# 5403833B.net
KiCad netlist of a schematic drawn in EAGLE
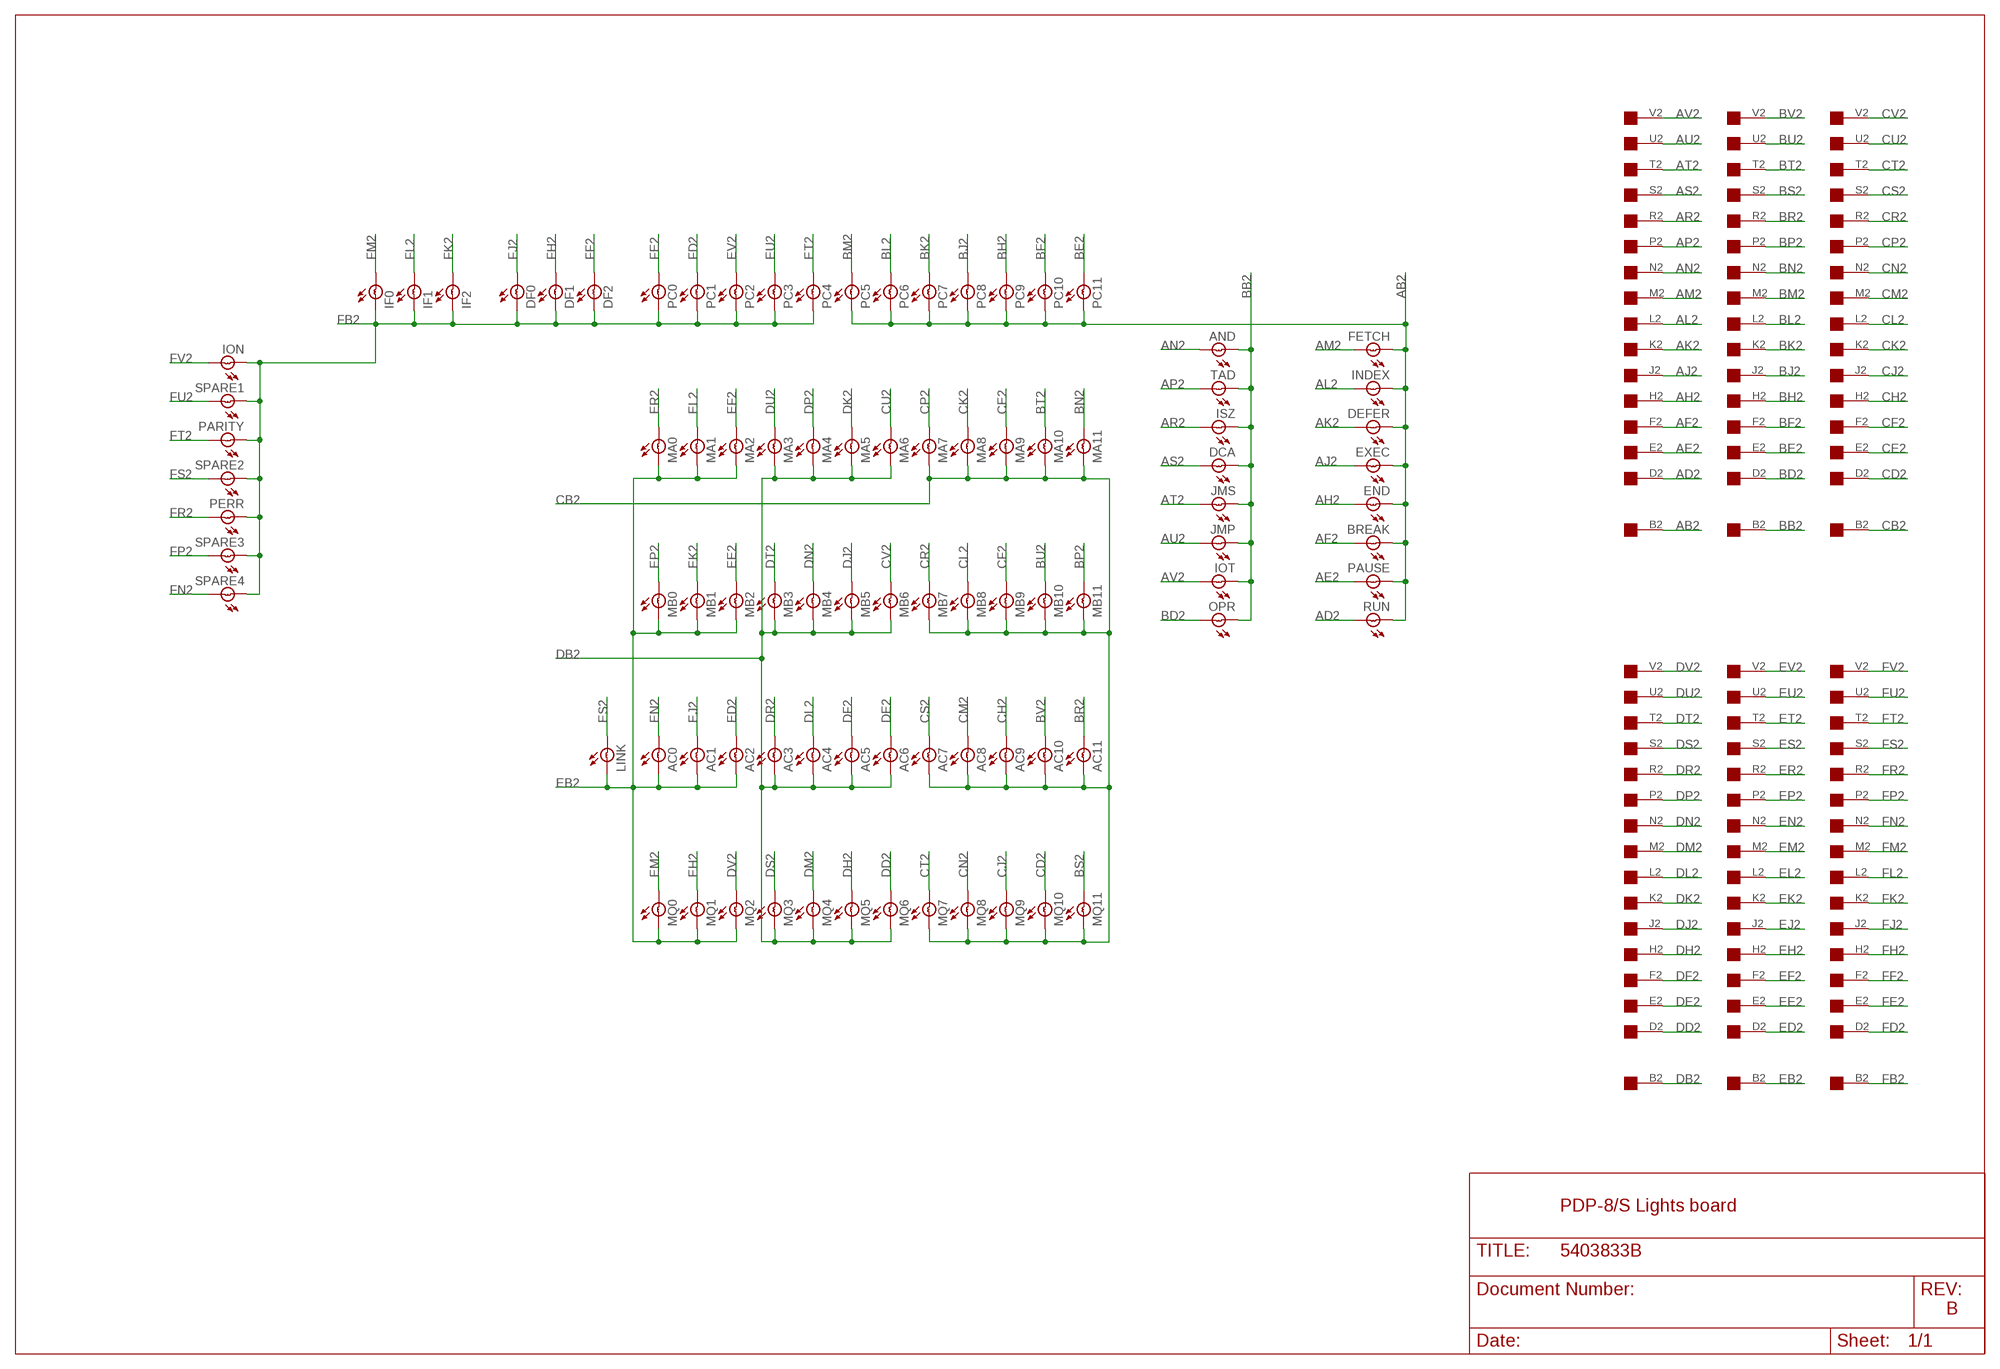
[diagram p0: schematic, sheet 1]

(export (version "E")
  (design (tool "Eeschema 10.0.6"))
  (components
    (comp (ref "A")
      (value "EDGE-1")
      (footprint "eagle-import:EDGE-CON1")
      (libsource (lib "eagle-import") (part "EDGE-1"))
    )
    (comp (ref "AC0")
      (value "BULB")
      (footprint "eagle-import:BULB")
      (libsource (lib "eagle-import") (part "BULB"))
    )
    (comp (ref "AC1")
      (value "BULB")
      (footprint "eagle-import:BULB")
      (libsource (lib "eagle-import") (part "BULB"))
    )
    (comp (ref "AC2")
      (value "BULB")
      (footprint "eagle-import:BULB")
      (libsource (lib "eagle-import") (part "BULB"))
    )
    (comp (ref "AC3")
      (value "BULB")
      (footprint "eagle-import:BULB")
      (libsource (lib "eagle-import") (part "BULB"))
    )
    (comp (ref "AC4")
      (value "BULB")
      (footprint "eagle-import:BULB")
      (libsource (lib "eagle-import") (part "BULB"))
    )
    (comp (ref "AC5")
      (value "BULB")
      (footprint "eagle-import:BULB")
      (libsource (lib "eagle-import") (part "BULB"))
    )
    (comp (ref "AC6")
      (value "BULB")
      (footprint "eagle-import:BULB")
      (libsource (lib "eagle-import") (part "BULB"))
    )
    (comp (ref "AC7")
      (value "BULB")
      (footprint "eagle-import:BULB")
      (libsource (lib "eagle-import") (part "BULB"))
    )
    (comp (ref "AC8")
      (value "BULB")
      (footprint "eagle-import:BULB")
      (libsource (lib "eagle-import") (part "BULB"))
    )
    (comp (ref "AC9")
      (value "BULB")
      (footprint "eagle-import:BULB")
      (libsource (lib "eagle-import") (part "BULB"))
    )
    (comp (ref "AC10")
      (value "BULB")
      (footprint "eagle-import:BULB")
      (libsource (lib "eagle-import") (part "BULB"))
    )
    (comp (ref "AC11")
      (value "BULB")
      (footprint "eagle-import:BULB")
      (libsource (lib "eagle-import") (part "BULB"))
    )
    (comp (ref "AND")
      (value "BULB")
      (footprint "eagle-import:BULB")
      (libsource (lib "eagle-import") (part "BULB"))
    )
    (comp (ref "B")
      (value "EDGE-1")
      (footprint "eagle-import:EDGE-CON1")
      (libsource (lib "eagle-import") (part "EDGE-1"))
    )
    (comp (ref "BREAK")
      (value "BULB")
      (footprint "eagle-import:BULB")
      (libsource (lib "eagle-import") (part "BULB"))
    )
    (comp (ref "C")
      (value "EDGE-1")
      (footprint "eagle-import:EDGE-CON1")
      (libsource (lib "eagle-import") (part "EDGE-1"))
    )
    (comp (ref "D")
      (value "EDGE-1")
      (footprint "eagle-import:EDGE-CON1")
      (libsource (lib "eagle-import") (part "EDGE-1"))
    )
    (comp (ref "DCA")
      (value "BULB")
      (footprint "eagle-import:BULB")
      (libsource (lib "eagle-import") (part "BULB"))
    )
    (comp (ref "DEFER")
      (value "BULB")
      (footprint "eagle-import:BULB")
      (libsource (lib "eagle-import") (part "BULB"))
    )
    (comp (ref "DF0")
      (value "BULB")
      (footprint "eagle-import:BULB")
      (libsource (lib "eagle-import") (part "BULB"))
    )
    (comp (ref "DF1")
      (value "BULB")
      (footprint "eagle-import:BULB")
      (libsource (lib "eagle-import") (part "BULB"))
    )
    (comp (ref "DF2")
      (value "BULB")
      (footprint "eagle-import:BULB")
      (libsource (lib "eagle-import") (part "BULB"))
    )
    (comp (ref "E")
      (value "EDGE-1")
      (footprint "eagle-import:EDGE-CON1")
      (libsource (lib "eagle-import") (part "EDGE-1"))
    )
    (comp (ref "END")
      (value "BULB")
      (footprint "eagle-import:BULB")
      (libsource (lib "eagle-import") (part "BULB"))
    )
    (comp (ref "EXEC")
      (value "BULB")
      (footprint "eagle-import:BULB")
      (libsource (lib "eagle-import") (part "BULB"))
    )
    (comp (ref "F")
      (value "EDGE-1")
      (footprint "eagle-import:EDGE-CON1")
      (libsource (lib "eagle-import") (part "EDGE-1"))
    )
    (comp (ref "FETCH")
      (value "BULB")
      (footprint "eagle-import:BULB")
      (libsource (lib "eagle-import") (part "BULB"))
    )
    (comp (ref "IF0")
      (value "BULB")
      (footprint "eagle-import:BULB")
      (libsource (lib "eagle-import") (part "BULB"))
    )
    (comp (ref "IF1")
      (value "BULB")
      (footprint "eagle-import:BULB")
      (libsource (lib "eagle-import") (part "BULB"))
    )
    (comp (ref "IF2")
      (value "BULB")
      (footprint "eagle-import:BULB")
      (libsource (lib "eagle-import") (part "BULB"))
    )
    (comp (ref "INDEX")
      (value "BULB")
      (footprint "eagle-import:BULB")
      (libsource (lib "eagle-import") (part "BULB"))
    )
    (comp (ref "ION")
      (value "BULB")
      (footprint "eagle-import:BULB")
      (libsource (lib "eagle-import") (part "BULB"))
    )
    (comp (ref "IOT")
      (value "BULB")
      (footprint "eagle-import:BULB")
      (libsource (lib "eagle-import") (part "BULB"))
    )
    (comp (ref "ISZ")
      (value "BULB")
      (footprint "eagle-import:BULB")
      (libsource (lib "eagle-import") (part "BULB"))
    )
    (comp (ref "JMP")
      (value "BULB")
      (footprint "eagle-import:BULB")
      (libsource (lib "eagle-import") (part "BULB"))
    )
    (comp (ref "JMS")
      (value "BULB")
      (footprint "eagle-import:BULB")
      (libsource (lib "eagle-import") (part "BULB"))
    )
    (comp (ref "LINK")
      (value "BULB")
      (footprint "eagle-import:BULB")
      (libsource (lib "eagle-import") (part "BULB"))
    )
    (comp (ref "MA0")
      (value "BULB")
      (footprint "eagle-import:BULB")
      (libsource (lib "eagle-import") (part "BULB"))
    )
    (comp (ref "MA1")
      (value "BULB")
      (footprint "eagle-import:BULB")
      (libsource (lib "eagle-import") (part "BULB"))
    )
    (comp (ref "MA2")
      (value "BULB")
      (footprint "eagle-import:BULB")
      (libsource (lib "eagle-import") (part "BULB"))
    )
    (comp (ref "MA3")
      (value "BULB")
      (footprint "eagle-import:BULB")
      (libsource (lib "eagle-import") (part "BULB"))
    )
    (comp (ref "MA4")
      (value "BULB")
      (footprint "eagle-import:BULB")
      (libsource (lib "eagle-import") (part "BULB"))
    )
    (comp (ref "MA5")
      (value "BULB")
      (footprint "eagle-import:BULB")
      (libsource (lib "eagle-import") (part "BULB"))
    )
    (comp (ref "MA6")
      (value "BULB")
      (footprint "eagle-import:BULB")
      (libsource (lib "eagle-import") (part "BULB"))
    )
    (comp (ref "MA7")
      (value "BULB")
      (footprint "eagle-import:BULB")
      (libsource (lib "eagle-import") (part "BULB"))
    )
    (comp (ref "MA8")
      (value "BULB")
      (footprint "eagle-import:BULB")
      (libsource (lib "eagle-import") (part "BULB"))
    )
    (comp (ref "MA9")
      (value "BULB")
      (footprint "eagle-import:BULB")
      (libsource (lib "eagle-import") (part "BULB"))
    )
    (comp (ref "MA10")
      (value "BULB")
      (footprint "eagle-import:BULB")
      (libsource (lib "eagle-import") (part "BULB"))
    )
    (comp (ref "MA11")
      (value "BULB")
      (footprint "eagle-import:BULB")
      (libsource (lib "eagle-import") (part "BULB"))
    )
    (comp (ref "MB0")
      (value "BULB")
      (footprint "eagle-import:BULB")
      (libsource (lib "eagle-import") (part "BULB"))
    )
    (comp (ref "MB1")
      (value "BULB")
      (footprint "eagle-import:BULB")
      (libsource (lib "eagle-import") (part "BULB"))
    )
    (comp (ref "MB2")
      (value "BULB")
      (footprint "eagle-import:BULB")
      (libsource (lib "eagle-import") (part "BULB"))
    )
    (comp (ref "MB3")
      (value "BULB")
      (footprint "eagle-import:BULB")
      (libsource (lib "eagle-import") (part "BULB"))
    )
    (comp (ref "MB4")
      (value "BULB")
      (footprint "eagle-import:BULB")
      (libsource (lib "eagle-import") (part "BULB"))
    )
    (comp (ref "MB5")
      (value "BULB")
      (footprint "eagle-import:BULB")
      (libsource (lib "eagle-import") (part "BULB"))
    )
    (comp (ref "MB6")
      (value "BULB")
      (footprint "eagle-import:BULB")
      (libsource (lib "eagle-import") (part "BULB"))
    )
    (comp (ref "MB7")
      (value "BULB")
      (footprint "eagle-import:BULB")
      (libsource (lib "eagle-import") (part "BULB"))
    )
    (comp (ref "MB8")
      (value "BULB")
      (footprint "eagle-import:BULB")
      (libsource (lib "eagle-import") (part "BULB"))
    )
    (comp (ref "MB9")
      (value "BULB")
      (footprint "eagle-import:BULB")
      (libsource (lib "eagle-import") (part "BULB"))
    )
    (comp (ref "MB10")
      (value "BULB")
      (footprint "eagle-import:BULB")
      (libsource (lib "eagle-import") (part "BULB"))
    )
    (comp (ref "MB11")
      (value "BULB")
      (footprint "eagle-import:BULB")
      (libsource (lib "eagle-import") (part "BULB"))
    )
    (comp (ref "MQ0")
      (value "BULB")
      (footprint "eagle-import:BULB")
      (libsource (lib "eagle-import") (part "BULB"))
    )
    (comp (ref "MQ1")
      (value "BULB")
      (footprint "eagle-import:BULB")
      (libsource (lib "eagle-import") (part "BULB"))
    )
    (comp (ref "MQ2")
      (value "BULB")
      (footprint "eagle-import:BULB")
      (libsource (lib "eagle-import") (part "BULB"))
    )
    (comp (ref "MQ3")
      (value "BULB")
      (footprint "eagle-import:BULB")
      (libsource (lib "eagle-import") (part "BULB"))
    )
    (comp (ref "MQ4")
      (value "BULB")
      (footprint "eagle-import:BULB")
      (libsource (lib "eagle-import") (part "BULB"))
    )
    (comp (ref "MQ5")
      (value "BULB")
      (footprint "eagle-import:BULB")
      (libsource (lib "eagle-import") (part "BULB"))
    )
    (comp (ref "MQ6")
      (value "BULB")
      (footprint "eagle-import:BULB")
      (libsource (lib "eagle-import") (part "BULB"))
    )
    (comp (ref "MQ7")
      (value "BULB")
      (footprint "eagle-import:BULB")
      (libsource (lib "eagle-import") (part "BULB"))
    )
    (comp (ref "MQ8")
      (value "BULB")
      (footprint "eagle-import:BULB")
      (libsource (lib "eagle-import") (part "BULB"))
    )
    (comp (ref "MQ9")
      (value "BULB")
      (footprint "eagle-import:BULB")
      (libsource (lib "eagle-import") (part "BULB"))
    )
    (comp (ref "MQ10")
      (value "BULB")
      (footprint "eagle-import:BULB")
      (libsource (lib "eagle-import") (part "BULB"))
    )
    (comp (ref "MQ11")
      (value "BULB")
      (footprint "eagle-import:BULB")
      (libsource (lib "eagle-import") (part "BULB"))
    )
    (comp (ref "OPR")
      (value "BULB")
      (footprint "eagle-import:BULB")
      (libsource (lib "eagle-import") (part "BULB"))
    )
    (comp (ref "PARITY")
      (value "BULB")
      (footprint "eagle-import:BULB")
      (libsource (lib "eagle-import") (part "BULB"))
    )
    (comp (ref "PAUSE")
      (value "BULB")
      (footprint "eagle-import:BULB")
      (libsource (lib "eagle-import") (part "BULB"))
    )
    (comp (ref "PC0")
      (value "BULB")
      (footprint "eagle-import:BULB")
      (libsource (lib "eagle-import") (part "BULB"))
    )
    (comp (ref "PC1")
      (value "BULB")
      (footprint "eagle-import:BULB")
      (libsource (lib "eagle-import") (part "BULB"))
    )
    (comp (ref "PC2")
      (value "BULB")
      (footprint "eagle-import:BULB")
      (libsource (lib "eagle-import") (part "BULB"))
    )
    (comp (ref "PC3")
      (value "BULB")
      (footprint "eagle-import:BULB")
      (libsource (lib "eagle-import") (part "BULB"))
    )
    (comp (ref "PC4")
      (value "BULB")
      (footprint "eagle-import:BULB")
      (libsource (lib "eagle-import") (part "BULB"))
    )
    (comp (ref "PC5")
      (value "BULB")
      (footprint "eagle-import:BULB")
      (libsource (lib "eagle-import") (part "BULB"))
    )
    (comp (ref "PC6")
      (value "BULB")
      (footprint "eagle-import:BULB")
      (libsource (lib "eagle-import") (part "BULB"))
    )
    (comp (ref "PC7")
      (value "BULB")
      (footprint "eagle-import:BULB")
      (libsource (lib "eagle-import") (part "BULB"))
    )
    (comp (ref "PC8")
      (value "BULB")
      (footprint "eagle-import:BULB")
      (libsource (lib "eagle-import") (part "BULB"))
    )
    (comp (ref "PC9")
      (value "BULB")
      (footprint "eagle-import:BULB")
      (libsource (lib "eagle-import") (part "BULB"))
    )
    (comp (ref "PC10")
      (value "BULB")
      (footprint "eagle-import:BULB")
      (libsource (lib "eagle-import") (part "BULB"))
    )
    (comp (ref "PC11")
      (value "BULB")
      (footprint "eagle-import:BULB")
      (libsource (lib "eagle-import") (part "BULB"))
    )
    (comp (ref "PERR")
      (value "BULB")
      (footprint "eagle-import:BULB")
      (libsource (lib "eagle-import") (part "BULB"))
    )
    (comp (ref "RUN")
      (value "BULB")
      (footprint "eagle-import:BULB")
      (libsource (lib "eagle-import") (part "BULB"))
    )
    (comp (ref "SPARE1")
      (value "BULB")
      (footprint "eagle-import:BULB")
      (libsource (lib "eagle-import") (part "BULB"))
    )
    (comp (ref "SPARE2")
      (value "BULB")
      (footprint "eagle-import:BULB")
      (libsource (lib "eagle-import") (part "BULB"))
    )
    (comp (ref "SPARE3")
      (value "BULB")
      (footprint "eagle-import:BULB")
      (libsource (lib "eagle-import") (part "BULB"))
    )
    (comp (ref "SPARE4")
      (value "BULB")
      (footprint "eagle-import:BULB")
      (libsource (lib "eagle-import") (part "BULB"))
    )
    (comp (ref "TAD")
      (value "BULB")
      (footprint "eagle-import:BULB")
      (libsource (lib "eagle-import") (part "BULB"))
    )
  )
  (nets
    (net (code "1") (name "/AB2") (class "Default")
      (node (ref "A") (pin "B2") (pinfunction "1_B2") (pintype "bidirectional"))
      (node (ref "BREAK") (pin "B") (pinfunction "B_B") (pintype "passive"))
      (node (ref "DEFER") (pin "B") (pinfunction "B_B") (pintype "passive"))
      (node (ref "END") (pin "B") (pinfunction "B_B") (pintype "passive"))
      (node (ref "EXEC") (pin "B") (pinfunction "B_B") (pintype "passive"))
      (node (ref "FETCH") (pin "B") (pinfunction "B_B") (pintype "passive"))
      (node (ref "INDEX") (pin "B") (pinfunction "B_B") (pintype "passive"))
      (node (ref "PAUSE") (pin "B") (pinfunction "B_B") (pintype "passive"))
      (node (ref "PC10") (pin "B") (pinfunction "B_B") (pintype "passive"))
      (node (ref "PC11") (pin "B") (pinfunction "B_B") (pintype "passive"))
      (node (ref "PC5") (pin "B") (pinfunction "B_B") (pintype "passive"))
      (node (ref "PC6") (pin "B") (pinfunction "B_B") (pintype "passive"))
      (node (ref "PC7") (pin "B") (pinfunction "B_B") (pintype "passive"))
      (node (ref "PC8") (pin "B") (pinfunction "B_B") (pintype "passive"))
      (node (ref "PC9") (pin "B") (pinfunction "B_B") (pintype "passive"))
      (node (ref "RUN") (pin "B") (pinfunction "B_B") (pintype "passive"))
    )
    (net (code "2") (name "/AD2") (class "Default")
      (node (ref "A") (pin "D2") (pinfunction "1_D2") (pintype "bidirectional"))
      (node (ref "RUN") (pin "A") (pinfunction "A_A") (pintype "passive"))
    )
    (net (code "3") (name "/AE2") (class "Default")
      (node (ref "A") (pin "E2") (pinfunction "1_E2") (pintype "bidirectional"))
      (node (ref "PAUSE") (pin "A") (pinfunction "A_A") (pintype "passive"))
    )
    (net (code "4") (name "/AF2") (class "Default")
      (node (ref "A") (pin "F2") (pinfunction "1_F2") (pintype "bidirectional"))
      (node (ref "BREAK") (pin "A") (pinfunction "A_A") (pintype "passive"))
    )
    (net (code "5") (name "/AH2") (class "Default")
      (node (ref "A") (pin "H2") (pinfunction "1_H2") (pintype "bidirectional"))
      (node (ref "END") (pin "A") (pinfunction "A_A") (pintype "passive"))
    )
    (net (code "6") (name "/AJ2") (class "Default")
      (node (ref "A") (pin "J2") (pinfunction "1_J2") (pintype "bidirectional"))
      (node (ref "EXEC") (pin "A") (pinfunction "A_A") (pintype "passive"))
    )
    (net (code "7") (name "/AK2") (class "Default")
      (node (ref "A") (pin "K2") (pinfunction "1_K2") (pintype "bidirectional"))
      (node (ref "DEFER") (pin "A") (pinfunction "A_A") (pintype "passive"))
    )
    (net (code "8") (name "/AL2") (class "Default")
      (node (ref "A") (pin "L2") (pinfunction "1_L2") (pintype "bidirectional"))
      (node (ref "INDEX") (pin "A") (pinfunction "A_A") (pintype "passive"))
    )
    (net (code "9") (name "/AM2") (class "Default")
      (node (ref "A") (pin "M2") (pinfunction "1_M2") (pintype "bidirectional"))
      (node (ref "FETCH") (pin "A") (pinfunction "A_A") (pintype "passive"))
    )
    (net (code "10") (name "/AN2") (class "Default")
      (node (ref "A") (pin "N2") (pinfunction "1_N2") (pintype "bidirectional"))
      (node (ref "AND") (pin "A") (pinfunction "A_A") (pintype "passive"))
    )
    (net (code "11") (name "/AP2") (class "Default")
      (node (ref "A") (pin "P2") (pinfunction "1_P2") (pintype "bidirectional"))
      (node (ref "TAD") (pin "A") (pinfunction "A_A") (pintype "passive"))
    )
    (net (code "12") (name "/AR2") (class "Default")
      (node (ref "A") (pin "R2") (pinfunction "1_R2") (pintype "bidirectional"))
      (node (ref "ISZ") (pin "A") (pinfunction "A_A") (pintype "passive"))
    )
    (net (code "13") (name "/AS2") (class "Default")
      (node (ref "A") (pin "S2") (pinfunction "1_S2") (pintype "bidirectional"))
      (node (ref "DCA") (pin "A") (pinfunction "A_A") (pintype "passive"))
    )
    (net (code "14") (name "/AT2") (class "Default")
      (node (ref "A") (pin "T2") (pinfunction "1_T2") (pintype "bidirectional"))
      (node (ref "JMS") (pin "A") (pinfunction "A_A") (pintype "passive"))
    )
    (net (code "15") (name "/AU2") (class "Default")
      (node (ref "A") (pin "U2") (pinfunction "1_U2") (pintype "bidirectional"))
      (node (ref "JMP") (pin "A") (pinfunction "A_A") (pintype "passive"))
    )
    (net (code "16") (name "/AV2") (class "Default")
      (node (ref "A") (pin "V2") (pinfunction "1_V2") (pintype "bidirectional"))
      (node (ref "IOT") (pin "A") (pinfunction "A_A") (pintype "passive"))
    )
    (net (code "17") (name "/BB2") (class "Default")
      (node (ref "AND") (pin "B") (pinfunction "B_B") (pintype "passive"))
      (node (ref "B") (pin "B2") (pinfunction "1_B2") (pintype "bidirectional"))
      (node (ref "DCA") (pin "B") (pinfunction "B_B") (pintype "passive"))
      (node (ref "IOT") (pin "B") (pinfunction "B_B") (pintype "passive"))
      (node (ref "ISZ") (pin "B") (pinfunction "B_B") (pintype "passive"))
      (node (ref "JMP") (pin "B") (pinfunction "B_B") (pintype "passive"))
      (node (ref "JMS") (pin "B") (pinfunction "B_B") (pintype "passive"))
      (node (ref "OPR") (pin "B") (pinfunction "B_B") (pintype "passive"))
      (node (ref "TAD") (pin "B") (pinfunction "B_B") (pintype "passive"))
    )
    (net (code "18") (name "/BD2") (class "Default")
      (node (ref "B") (pin "D2") (pinfunction "1_D2") (pintype "bidirectional"))
      (node (ref "OPR") (pin "A") (pinfunction "A_A") (pintype "passive"))
    )
    (net (code "19") (name "/BE2") (class "Default")
      (node (ref "B") (pin "E2") (pinfunction "1_E2") (pintype "bidirectional"))
      (node (ref "PC11") (pin "A") (pinfunction "A_A") (pintype "passive"))
    )
    (net (code "20") (name "/BF2") (class "Default")
      (node (ref "B") (pin "F2") (pinfunction "1_F2") (pintype "bidirectional"))
      (node (ref "PC10") (pin "A") (pinfunction "A_A") (pintype "passive"))
    )
    (net (code "21") (name "/BH2") (class "Default")
      (node (ref "B") (pin "H2") (pinfunction "1_H2") (pintype "bidirectional"))
      (node (ref "PC9") (pin "A") (pinfunction "A_A") (pintype "passive"))
    )
    (net (code "22") (name "/BJ2") (class "Default")
      (node (ref "B") (pin "J2") (pinfunction "1_J2") (pintype "bidirectional"))
      (node (ref "PC8") (pin "A") (pinfunction "A_A") (pintype "passive"))
    )
    (net (code "23") (name "/BK2") (class "Default")
      (node (ref "B") (pin "K2") (pinfunction "1_K2") (pintype "bidirectional"))
      (node (ref "PC7") (pin "A") (pinfunction "A_A") (pintype "passive"))
    )
    (net (code "24") (name "/BL2") (class "Default")
      (node (ref "B") (pin "L2") (pinfunction "1_L2") (pintype "bidirectional"))
      (node (ref "PC6") (pin "A") (pinfunction "A_A") (pintype "passive"))
    )
    (net (code "25") (name "/BM2") (class "Default")
      (node (ref "B") (pin "M2") (pinfunction "1_M2") (pintype "bidirectional"))
      (node (ref "PC5") (pin "A") (pinfunction "A_A") (pintype "passive"))
    )
    (net (code "26") (name "/BN2") (class "Default")
      (node (ref "B") (pin "N2") (pinfunction "1_N2") (pintype "bidirectional"))
      (node (ref "MA11") (pin "A") (pinfunction "A_A") (pintype "passive"))
    )
    (net (code "27") (name "/BP2") (class "Default")
      (node (ref "B") (pin "P2") (pinfunction "1_P2") (pintype "bidirectional"))
      (node (ref "MB11") (pin "A") (pinfunction "A_A") (pintype "passive"))
    )
    (net (code "28") (name "/BR2") (class "Default")
      (node (ref "AC11") (pin "A") (pinfunction "A_A") (pintype "passive"))
      (node (ref "B") (pin "R2") (pinfunction "1_R2") (pintype "bidirectional"))
    )
    (net (code "29") (name "/BS2") (class "Default")
      (node (ref "B") (pin "S2") (pinfunction "1_S2") (pintype "bidirectional"))
      (node (ref "MQ11") (pin "A") (pinfunction "A_A") (pintype "passive"))
    )
    (net (code "30") (name "/BT2") (class "Default")
      (node (ref "B") (pin "T2") (pinfunction "1_T2") (pintype "bidirectional"))
      (node (ref "MA10") (pin "A") (pinfunction "A_A") (pintype "passive"))
    )
    (net (code "31") (name "/BU2") (class "Default")
      (node (ref "B") (pin "U2") (pinfunction "1_U2") (pintype "bidirectional"))
      (node (ref "MB10") (pin "A") (pinfunction "A_A") (pintype "passive"))
    )
    (net (code "32") (name "/BV2") (class "Default")
      (node (ref "AC10") (pin "A") (pinfunction "A_A") (pintype "passive"))
      (node (ref "B") (pin "V2") (pinfunction "1_V2") (pintype "bidirectional"))
    )
    (net (code "33") (name "/CB2") (class "Default")
      (node (ref "AC10") (pin "B") (pinfunction "B_B") (pintype "passive"))
      (node (ref "AC11") (pin "B") (pinfunction "B_B") (pintype "passive"))
      (node (ref "AC7") (pin "B") (pinfunction "B_B") (pintype "passive"))
      (node (ref "AC8") (pin "B") (pinfunction "B_B") (pintype "passive"))
      (node (ref "AC9") (pin "B") (pinfunction "B_B") (pintype "passive"))
      (node (ref "C") (pin "B2") (pinfunction "1_B2") (pintype "bidirectional"))
      (node (ref "MA10") (pin "B") (pinfunction "B_B") (pintype "passive"))
      (node (ref "MA11") (pin "B") (pinfunction "B_B") (pintype "passive"))
      (node (ref "MA7") (pin "B") (pinfunction "B_B") (pintype "passive"))
      (node (ref "MA8") (pin "B") (pinfunction "B_B") (pintype "passive"))
      (node (ref "MA9") (pin "B") (pinfunction "B_B") (pintype "passive"))
      (node (ref "MB10") (pin "B") (pinfunction "B_B") (pintype "passive"))
      (node (ref "MB11") (pin "B") (pinfunction "B_B") (pintype "passive"))
      (node (ref "MB7") (pin "B") (pinfunction "B_B") (pintype "passive"))
      (node (ref "MB8") (pin "B") (pinfunction "B_B") (pintype "passive"))
      (node (ref "MB9") (pin "B") (pinfunction "B_B") (pintype "passive"))
      (node (ref "MQ10") (pin "B") (pinfunction "B_B") (pintype "passive"))
      (node (ref "MQ11") (pin "B") (pinfunction "B_B") (pintype "passive"))
      (node (ref "MQ7") (pin "B") (pinfunction "B_B") (pintype "passive"))
      (node (ref "MQ8") (pin "B") (pinfunction "B_B") (pintype "passive"))
      (node (ref "MQ9") (pin "B") (pinfunction "B_B") (pintype "passive"))
    )
    (net (code "34") (name "/CD2") (class "Default")
      (node (ref "C") (pin "D2") (pinfunction "1_D2") (pintype "bidirectional"))
      (node (ref "MQ10") (pin "A") (pinfunction "A_A") (pintype "passive"))
    )
    (net (code "35") (name "/CE2") (class "Default")
      (node (ref "C") (pin "E2") (pinfunction "1_E2") (pintype "bidirectional"))
      (node (ref "MA9") (pin "A") (pinfunction "A_A") (pintype "passive"))
    )
    (net (code "36") (name "/CF2") (class "Default")
      (node (ref "C") (pin "F2") (pinfunction "1_F2") (pintype "bidirectional"))
      (node (ref "MB9") (pin "A") (pinfunction "A_A") (pintype "passive"))
    )
    (net (code "37") (name "/CH2") (class "Default")
      (node (ref "AC9") (pin "A") (pinfunction "A_A") (pintype "passive"))
      (node (ref "C") (pin "H2") (pinfunction "1_H2") (pintype "bidirectional"))
    )
    (net (code "38") (name "/CJ2") (class "Default")
      (node (ref "C") (pin "J2") (pinfunction "1_J2") (pintype "bidirectional"))
      (node (ref "MQ9") (pin "A") (pinfunction "A_A") (pintype "passive"))
    )
    (net (code "39") (name "/CK2") (class "Default")
      (node (ref "C") (pin "K2") (pinfunction "1_K2") (pintype "bidirectional"))
      (node (ref "MA8") (pin "A") (pinfunction "A_A") (pintype "passive"))
    )
    (net (code "40") (name "/CL2") (class "Default")
      (node (ref "C") (pin "L2") (pinfunction "1_L2") (pintype "bidirectional"))
      (node (ref "MB8") (pin "A") (pinfunction "A_A") (pintype "passive"))
    )
    (net (code "41") (name "/CM2") (class "Default")
      (node (ref "AC8") (pin "A") (pinfunction "A_A") (pintype "passive"))
      (node (ref "C") (pin "M2") (pinfunction "1_M2") (pintype "bidirectional"))
    )
    (net (code "42") (name "/CN2") (class "Default")
      (node (ref "C") (pin "N2") (pinfunction "1_N2") (pintype "bidirectional"))
      (node (ref "MQ8") (pin "A") (pinfunction "A_A") (pintype "passive"))
    )
    (net (code "43") (name "/CP2") (class "Default")
      (node (ref "C") (pin "P2") (pinfunction "1_P2") (pintype "bidirectional"))
      (node (ref "MA7") (pin "A") (pinfunction "A_A") (pintype "passive"))
    )
    (net (code "44") (name "/CR2") (class "Default")
      (node (ref "C") (pin "R2") (pinfunction "1_R2") (pintype "bidirectional"))
      (node (ref "MB7") (pin "A") (pinfunction "A_A") (pintype "passive"))
    )
    (net (code "45") (name "/CS2") (class "Default")
      (node (ref "AC7") (pin "A") (pinfunction "A_A") (pintype "passive"))
      (node (ref "C") (pin "S2") (pinfunction "1_S2") (pintype "bidirectional"))
    )
    (net (code "46") (name "/CT2") (class "Default")
      (node (ref "C") (pin "T2") (pinfunction "1_T2") (pintype "bidirectional"))
      (node (ref "MQ7") (pin "A") (pinfunction "A_A") (pintype "passive"))
    )
    (net (code "47") (name "/CU2") (class "Default")
      (node (ref "C") (pin "U2") (pinfunction "1_U2") (pintype "bidirectional"))
      (node (ref "MA6") (pin "A") (pinfunction "A_A") (pintype "passive"))
    )
    (net (code "48") (name "/CV2") (class "Default")
      (node (ref "C") (pin "V2") (pinfunction "1_V2") (pintype "bidirectional"))
      (node (ref "MB6") (pin "A") (pinfunction "A_A") (pintype "passive"))
    )
    (net (code "49") (name "/DB2") (class "Default")
      (node (ref "AC3") (pin "B") (pinfunction "B_B") (pintype "passive"))
      (node (ref "AC4") (pin "B") (pinfunction "B_B") (pintype "passive"))
      (node (ref "AC5") (pin "B") (pinfunction "B_B") (pintype "passive"))
      (node (ref "AC6") (pin "B") (pinfunction "B_B") (pintype "passive"))
      (node (ref "D") (pin "B2") (pinfunction "1_B2") (pintype "bidirectional"))
      (node (ref "MA3") (pin "B") (pinfunction "B_B") (pintype "passive"))
      (node (ref "MA4") (pin "B") (pinfunction "B_B") (pintype "passive"))
      (node (ref "MA5") (pin "B") (pinfunction "B_B") (pintype "passive"))
      (node (ref "MA6") (pin "B") (pinfunction "B_B") (pintype "passive"))
      (node (ref "MB3") (pin "B") (pinfunction "B_B") (pintype "passive"))
      (node (ref "MB4") (pin "B") (pinfunction "B_B") (pintype "passive"))
      (node (ref "MB5") (pin "B") (pinfunction "B_B") (pintype "passive"))
      (node (ref "MB6") (pin "B") (pinfunction "B_B") (pintype "passive"))
      (node (ref "MQ3") (pin "B") (pinfunction "B_B") (pintype "passive"))
      (node (ref "MQ4") (pin "B") (pinfunction "B_B") (pintype "passive"))
      (node (ref "MQ5") (pin "B") (pinfunction "B_B") (pintype "passive"))
      (node (ref "MQ6") (pin "B") (pinfunction "B_B") (pintype "passive"))
    )
    (net (code "50") (name "/DD2") (class "Default")
      (node (ref "D") (pin "D2") (pinfunction "1_D2") (pintype "bidirectional"))
      (node (ref "MQ6") (pin "A") (pinfunction "A_A") (pintype "passive"))
    )
    (net (code "51") (name "/DE2") (class "Default")
      (node (ref "AC6") (pin "A") (pinfunction "A_A") (pintype "passive"))
      (node (ref "D") (pin "E2") (pinfunction "1_E2") (pintype "bidirectional"))
    )
    (net (code "52") (name "/DF2") (class "Default")
      (node (ref "AC5") (pin "A") (pinfunction "A_A") (pintype "passive"))
      (node (ref "D") (pin "F2") (pinfunction "1_F2") (pintype "bidirectional"))
    )
    (net (code "53") (name "/DH2") (class "Default")
      (node (ref "D") (pin "H2") (pinfunction "1_H2") (pintype "bidirectional"))
      (node (ref "MQ5") (pin "A") (pinfunction "A_A") (pintype "passive"))
    )
    (net (code "54") (name "/DJ2") (class "Default")
      (node (ref "D") (pin "J2") (pinfunction "1_J2") (pintype "bidirectional"))
      (node (ref "MB5") (pin "A") (pinfunction "A_A") (pintype "passive"))
    )
    (net (code "55") (name "/DK2") (class "Default")
      (node (ref "D") (pin "K2") (pinfunction "1_K2") (pintype "bidirectional"))
      (node (ref "MA5") (pin "A") (pinfunction "A_A") (pintype "passive"))
    )
    (net (code "56") (name "/DL2") (class "Default")
      (node (ref "AC4") (pin "A") (pinfunction "A_A") (pintype "passive"))
      (node (ref "D") (pin "L2") (pinfunction "1_L2") (pintype "bidirectional"))
    )
    (net (code "57") (name "/DM2") (class "Default")
      (node (ref "D") (pin "M2") (pinfunction "1_M2") (pintype "bidirectional"))
      (node (ref "MQ4") (pin "A") (pinfunction "A_A") (pintype "passive"))
    )
    (net (code "58") (name "/DN2") (class "Default")
      (node (ref "D") (pin "N2") (pinfunction "1_N2") (pintype "bidirectional"))
      (node (ref "MB4") (pin "A") (pinfunction "A_A") (pintype "passive"))
    )
    (net (code "59") (name "/DP2") (class "Default")
      (node (ref "D") (pin "P2") (pinfunction "1_P2") (pintype "bidirectional"))
      (node (ref "MA4") (pin "A") (pinfunction "A_A") (pintype "passive"))
    )
    (net (code "60") (name "/DR2") (class "Default")
      (node (ref "AC3") (pin "A") (pinfunction "A_A") (pintype "passive"))
      (node (ref "D") (pin "R2") (pinfunction "1_R2") (pintype "bidirectional"))
    )
    (net (code "61") (name "/DS2") (class "Default")
      (node (ref "D") (pin "S2") (pinfunction "1_S2") (pintype "bidirectional"))
      (node (ref "MQ3") (pin "A") (pinfunction "A_A") (pintype "passive"))
    )
    (net (code "62") (name "/DT2") (class "Default")
      (node (ref "D") (pin "T2") (pinfunction "1_T2") (pintype "bidirectional"))
      (node (ref "MB3") (pin "A") (pinfunction "A_A") (pintype "passive"))
    )
    (net (code "63") (name "/DU2") (class "Default")
      (node (ref "D") (pin "U2") (pinfunction "1_U2") (pintype "bidirectional"))
      (node (ref "MA3") (pin "A") (pinfunction "A_A") (pintype "passive"))
    )
    (net (code "64") (name "/DV2") (class "Default")
      (node (ref "D") (pin "V2") (pinfunction "1_V2") (pintype "bidirectional"))
      (node (ref "MQ2") (pin "A") (pinfunction "A_A") (pintype "passive"))
    )
    (net (code "65") (name "/EB2") (class "Default")
      (node (ref "AC0") (pin "B") (pinfunction "B_B") (pintype "passive"))
      (node (ref "AC1") (pin "B") (pinfunction "B_B") (pintype "passive"))
      (node (ref "AC2") (pin "B") (pinfunction "B_B") (pintype "passive"))
      (node (ref "E") (pin "B2") (pinfunction "1_B2") (pintype "bidirectional"))
      (node (ref "LINK") (pin "B") (pinfunction "B_B") (pintype "passive"))
      (node (ref "MA0") (pin "B") (pinfunction "B_B") (pintype "passive"))
      (node (ref "MA1") (pin "B") (pinfunction "B_B") (pintype "passive"))
      (node (ref "MA2") (pin "B") (pinfunction "B_B") (pintype "passive"))
      (node (ref "MB0") (pin "B") (pinfunction "B_B") (pintype "passive"))
      (node (ref "MB1") (pin "B") (pinfunction "B_B") (pintype "passive"))
      (node (ref "MB2") (pin "B") (pinfunction "B_B") (pintype "passive"))
      (node (ref "MQ0") (pin "B") (pinfunction "B_B") (pintype "passive"))
      (node (ref "MQ1") (pin "B") (pinfunction "B_B") (pintype "passive"))
      (node (ref "MQ2") (pin "B") (pinfunction "B_B") (pintype "passive"))
    )
    (net (code "66") (name "/ED2") (class "Default")
      (node (ref "AC2") (pin "A") (pinfunction "A_A") (pintype "passive"))
      (node (ref "E") (pin "D2") (pinfunction "1_D2") (pintype "bidirectional"))
    )
    (net (code "67") (name "/EE2") (class "Default")
      (node (ref "E") (pin "E2") (pinfunction "1_E2") (pintype "bidirectional"))
      (node (ref "MB2") (pin "A") (pinfunction "A_A") (pintype "passive"))
    )
    (net (code "68") (name "/EF2") (class "Default")
      (node (ref "E") (pin "F2") (pinfunction "1_F2") (pintype "bidirectional"))
      (node (ref "MA2") (pin "A") (pinfunction "A_A") (pintype "passive"))
    )
    (net (code "69") (name "/EH2") (class "Default")
      (node (ref "E") (pin "H2") (pinfunction "1_H2") (pintype "bidirectional"))
      (node (ref "MQ1") (pin "A") (pinfunction "A_A") (pintype "passive"))
    )
    (net (code "70") (name "/EJ2") (class "Default")
      (node (ref "AC1") (pin "A") (pinfunction "A_A") (pintype "passive"))
      (node (ref "E") (pin "J2") (pinfunction "1_J2") (pintype "bidirectional"))
    )
    (net (code "71") (name "/EK2") (class "Default")
      (node (ref "E") (pin "K2") (pinfunction "1_K2") (pintype "bidirectional"))
      (node (ref "MB1") (pin "A") (pinfunction "A_A") (pintype "passive"))
    )
    (net (code "72") (name "/EL2") (class "Default")
      (node (ref "E") (pin "L2") (pinfunction "1_L2") (pintype "bidirectional"))
      (node (ref "MA1") (pin "A") (pinfunction "A_A") (pintype "passive"))
    )
    (net (code "73") (name "/EM2") (class "Default")
      (node (ref "E") (pin "M2") (pinfunction "1_M2") (pintype "bidirectional"))
      (node (ref "MQ0") (pin "A") (pinfunction "A_A") (pintype "passive"))
    )
    (net (code "74") (name "/EN2") (class "Default")
      (node (ref "AC0") (pin "A") (pinfunction "A_A") (pintype "passive"))
      (node (ref "E") (pin "N2") (pinfunction "1_N2") (pintype "bidirectional"))
    )
    (net (code "75") (name "/EP2") (class "Default")
      (node (ref "E") (pin "P2") (pinfunction "1_P2") (pintype "bidirectional"))
      (node (ref "MB0") (pin "A") (pinfunction "A_A") (pintype "passive"))
    )
    (net (code "76") (name "/ER2") (class "Default")
      (node (ref "E") (pin "R2") (pinfunction "1_R2") (pintype "bidirectional"))
      (node (ref "MA0") (pin "A") (pinfunction "A_A") (pintype "passive"))
    )
    (net (code "77") (name "/ES2") (class "Default")
      (node (ref "E") (pin "S2") (pinfunction "1_S2") (pintype "bidirectional"))
      (node (ref "LINK") (pin "A") (pinfunction "A_A") (pintype "passive"))
    )
    (net (code "78") (name "/ET2") (class "Default")
      (node (ref "E") (pin "T2") (pinfunction "1_T2") (pintype "bidirectional"))
      (node (ref "PC4") (pin "A") (pinfunction "A_A") (pintype "passive"))
    )
    (net (code "79") (name "/EU2") (class "Default")
      (node (ref "E") (pin "U2") (pinfunction "1_U2") (pintype "bidirectional"))
      (node (ref "PC3") (pin "A") (pinfunction "A_A") (pintype "passive"))
    )
    (net (code "80") (name "/EV2") (class "Default")
      (node (ref "E") (pin "V2") (pinfunction "1_V2") (pintype "bidirectional"))
      (node (ref "PC2") (pin "A") (pinfunction "A_A") (pintype "passive"))
    )
    (net (code "81") (name "/FB2") (class "Default")
      (node (ref "DF0") (pin "B") (pinfunction "B_B") (pintype "passive"))
      (node (ref "DF1") (pin "B") (pinfunction "B_B") (pintype "passive"))
      (node (ref "DF2") (pin "B") (pinfunction "B_B") (pintype "passive"))
      (node (ref "F") (pin "B2") (pinfunction "1_B2") (pintype "bidirectional"))
      (node (ref "IF0") (pin "B") (pinfunction "B_B") (pintype "passive"))
      (node (ref "IF1") (pin "B") (pinfunction "B_B") (pintype "passive"))
      (node (ref "IF2") (pin "B") (pinfunction "B_B") (pintype "passive"))
      (node (ref "ION") (pin "B") (pinfunction "B_B") (pintype "passive"))
      (node (ref "PARITY") (pin "B") (pinfunction "B_B") (pintype "passive"))
      (node (ref "PC0") (pin "B") (pinfunction "B_B") (pintype "passive"))
      (node (ref "PC1") (pin "B") (pinfunction "B_B") (pintype "passive"))
      (node (ref "PC2") (pin "B") (pinfunction "B_B") (pintype "passive"))
      (node (ref "PC3") (pin "B") (pinfunction "B_B") (pintype "passive"))
      (node (ref "PC4") (pin "B") (pinfunction "B_B") (pintype "passive"))
      (node (ref "PERR") (pin "B") (pinfunction "B_B") (pintype "passive"))
      (node (ref "SPARE1") (pin "B") (pinfunction "B_B") (pintype "passive"))
      (node (ref "SPARE2") (pin "B") (pinfunction "B_B") (pintype "passive"))
      (node (ref "SPARE3") (pin "B") (pinfunction "B_B") (pintype "passive"))
      (node (ref "SPARE4") (pin "B") (pinfunction "B_B") (pintype "passive"))
    )
    (net (code "82") (name "/FD2") (class "Default")
      (node (ref "F") (pin "D2") (pinfunction "1_D2") (pintype "bidirectional"))
      (node (ref "PC1") (pin "A") (pinfunction "A_A") (pintype "passive"))
    )
    (net (code "83") (name "/FE2") (class "Default")
      (node (ref "F") (pin "E2") (pinfunction "1_E2") (pintype "bidirectional"))
      (node (ref "PC0") (pin "A") (pinfunction "A_A") (pintype "passive"))
    )
    (net (code "84") (name "/FF2") (class "Default")
      (node (ref "DF2") (pin "A") (pinfunction "A_A") (pintype "passive"))
      (node (ref "F") (pin "F2") (pinfunction "1_F2") (pintype "bidirectional"))
    )
    (net (code "85") (name "/FH2") (class "Default")
      (node (ref "DF1") (pin "A") (pinfunction "A_A") (pintype "passive"))
      (node (ref "F") (pin "H2") (pinfunction "1_H2") (pintype "bidirectional"))
    )
    (net (code "86") (name "/FJ2") (class "Default")
      (node (ref "DF0") (pin "A") (pinfunction "A_A") (pintype "passive"))
      (node (ref "F") (pin "J2") (pinfunction "1_J2") (pintype "bidirectional"))
    )
    (net (code "87") (name "/FK2") (class "Default")
      (node (ref "F") (pin "K2") (pinfunction "1_K2") (pintype "bidirectional"))
      (node (ref "IF2") (pin "A") (pinfunction "A_A") (pintype "passive"))
    )
    (net (code "88") (name "/FL2") (class "Default")
      (node (ref "F") (pin "L2") (pinfunction "1_L2") (pintype "bidirectional"))
      (node (ref "IF1") (pin "A") (pinfunction "A_A") (pintype "passive"))
    )
    (net (code "89") (name "/FM2") (class "Default")
      (node (ref "F") (pin "M2") (pinfunction "1_M2") (pintype "bidirectional"))
      (node (ref "IF0") (pin "A") (pinfunction "A_A") (pintype "passive"))
    )
    (net (code "90") (name "/FN2") (class "Default")
      (node (ref "F") (pin "N2") (pinfunction "1_N2") (pintype "bidirectional"))
      (node (ref "SPARE4") (pin "A") (pinfunction "A_A") (pintype "passive"))
    )
    (net (code "91") (name "/FP2") (class "Default")
      (node (ref "F") (pin "P2") (pinfunction "1_P2") (pintype "bidirectional"))
      (node (ref "SPARE3") (pin "A") (pinfunction "A_A") (pintype "passive"))
    )
    (net (code "92") (name "/FR2") (class "Default")
      (node (ref "F") (pin "R2") (pinfunction "1_R2") (pintype "bidirectional"))
      (node (ref "PERR") (pin "A") (pinfunction "A_A") (pintype "passive"))
    )
    (net (code "93") (name "/FS2") (class "Default")
      (node (ref "F") (pin "S2") (pinfunction "1_S2") (pintype "bidirectional"))
      (node (ref "SPARE2") (pin "A") (pinfunction "A_A") (pintype "passive"))
    )
    (net (code "94") (name "/FT2") (class "Default")
      (node (ref "F") (pin "T2") (pinfunction "1_T2") (pintype "bidirectional"))
      (node (ref "PARITY") (pin "A") (pinfunction "A_A") (pintype "passive"))
    )
    (net (code "95") (name "/FU2") (class "Default")
      (node (ref "F") (pin "U2") (pinfunction "1_U2") (pintype "bidirectional"))
      (node (ref "SPARE1") (pin "A") (pinfunction "A_A") (pintype "passive"))
    )
    (net (code "96") (name "/FV2") (class "Default")
      (node (ref "F") (pin "V2") (pinfunction "1_V2") (pintype "bidirectional"))
      (node (ref "ION") (pin "A") (pinfunction "A_A") (pintype "passive"))
    )
  )
)
